# LPS_main.net
KiCad netlist of a schematic drawn in Altium Designer
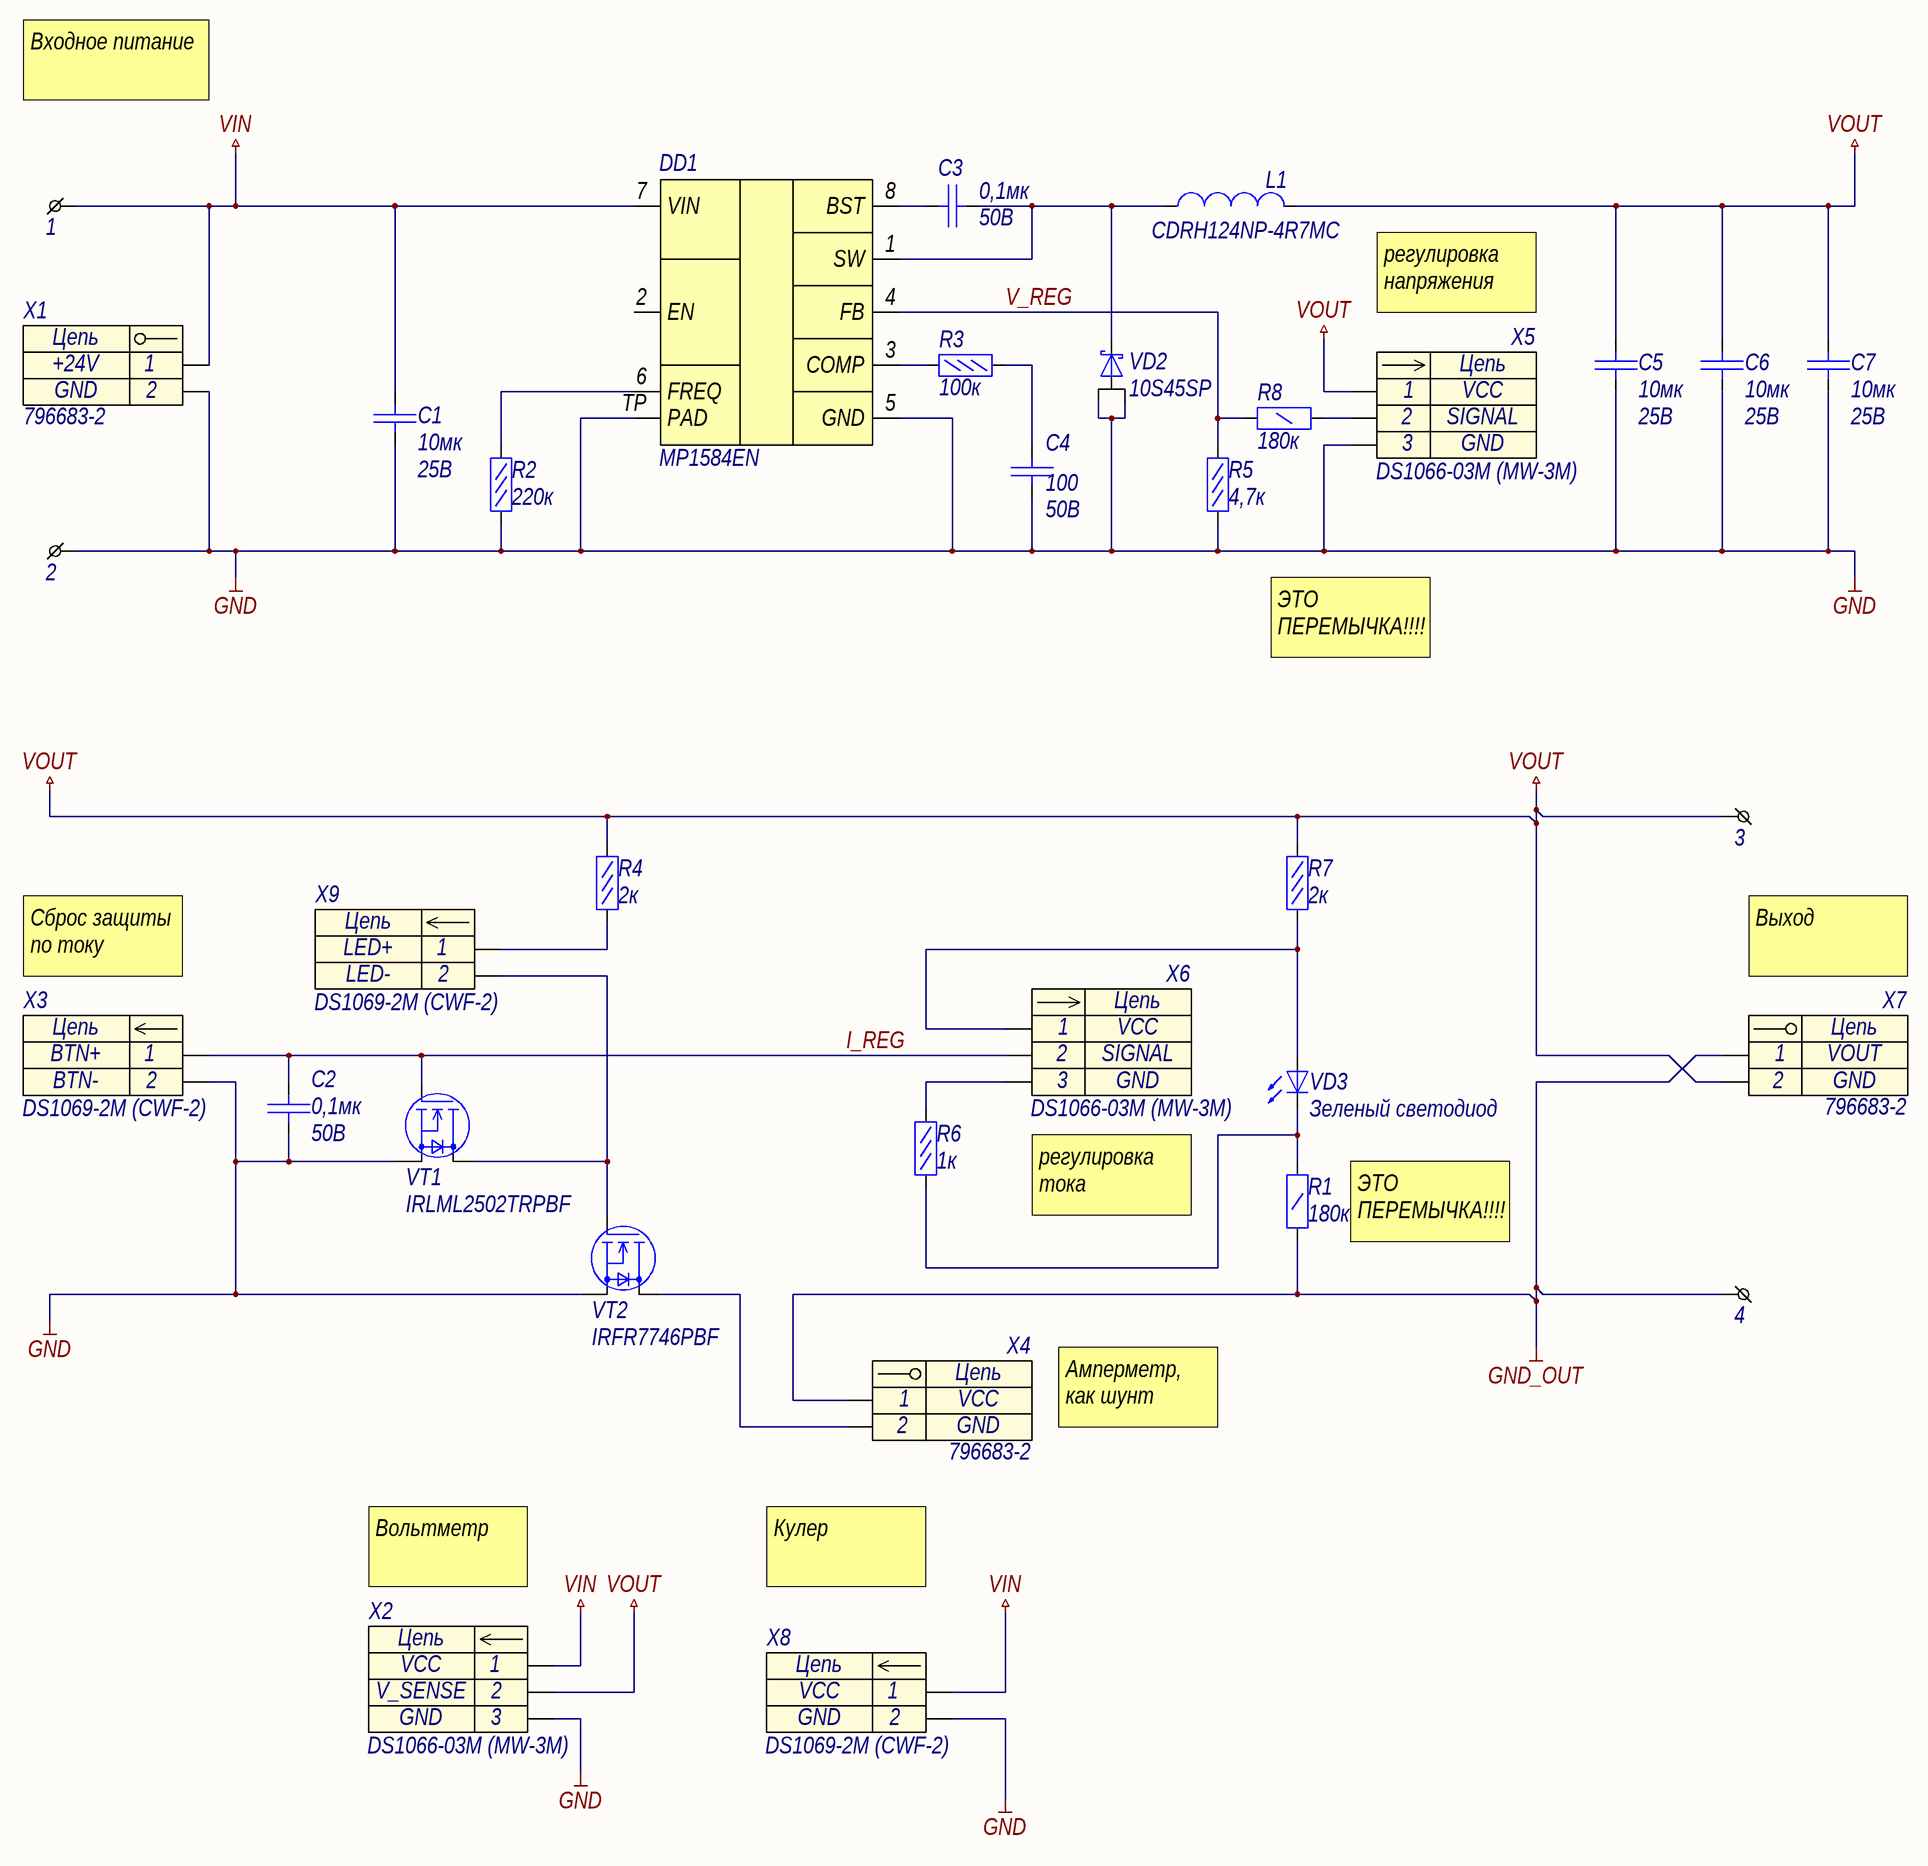
[diagram p0: LPS_main.SchDoc]

(export (version "E")
  (design (tool "Eeschema 10.0.6"))
  (components
    (comp (ref "1")
      (value "SOLDER_PAD")
      (footprint "PAD_5_8mm")
      (libsource (lib "mount_parts") (part "SOLDER_PAD"))
    )
    (comp (ref "2")
      (value "SOLDER_PAD")
      (footprint "PAD_5_8mm")
      (libsource (lib "mount_parts") (part "SOLDER_PAD"))
    )
    (comp (ref "3")
      (value "SOLDER_PAD")
      (footprint "PAD_5_8mm")
      (libsource (lib "mount_parts") (part "SOLDER_PAD"))
    )
    (comp (ref "4")
      (value "SOLDER_PAD")
      (footprint "PAD_5_8mm")
      (libsource (lib "mount_parts") (part "SOLDER_PAD"))
    )
    (comp (ref "C1")
      (value "10мк")
      (footprint "C1206")
      (description "Конденсатор кер. 10мкФ 25В")
      (fields (field (name "MANUFACTURER") "Yageo") (field (name "VOLTAGE") "25В"))
      (libsource (lib "capacitors") (part "CC1206KKX7R8BB106"))
    )
    (comp (ref "C2")
      (value "0,1мк")
      (footprint "C0603")
      (description "Конденсатор кер. 0,1мкФ 50В")
      (fields (field (name "MANUFACTURER") "Yageo") (field (name "VOLTAGE") "50В"))
      (libsource (lib "capacitors") (part "CC0603JPX7R9BB104"))
    )
    (comp (ref "C3")
      (value "0,1мк")
      (footprint "C0603")
      (description "Конденсатор кер. 0,1мкФ 50В")
      (fields (field (name "MANUFACTURER") "Yageo") (field (name "VOLTAGE") "50В"))
      (libsource (lib "capacitors") (part "CC0603JPX7R9BB104"))
    )
    (comp (ref "C4")
      (value "100")
      (footprint "C0603")
      (description "Конденсатор кер. 100пФ 50В")
      (fields (field (name "MANUFACTURER") "Yageo") (field (name "VOLTAGE") "50В"))
      (libsource (lib "capacitors") (part "CC0603JRNPO9BN101"))
    )
    (comp (ref "C5")
      (value "10мк")
      (footprint "C1206")
      (description "Конденсатор кер. 10мкФ 25В")
      (fields (field (name "MANUFACTURER") "Yageo") (field (name "VOLTAGE") "25В"))
      (libsource (lib "capacitors") (part "CC1206KKX7R8BB106"))
    )
    (comp (ref "C6")
      (value "10мк")
      (footprint "C1206")
      (description "Конденсатор кер. 10мкФ 25В")
      (fields (field (name "MANUFACTURER") "Yageo") (field (name "VOLTAGE") "25В"))
      (libsource (lib "capacitors") (part "CC1206KKX7R8BB106"))
    )
    (comp (ref "C7")
      (value "10мк")
      (footprint "C1206")
      (description "Конденсатор кер. 10мкФ 25В")
      (fields (field (name "MANUFACTURER") "Yageo") (field (name "VOLTAGE") "25В"))
      (libsource (lib "capacitors") (part "CC1206KKX7R8BB106"))
    )
    (comp (ref "DD1")
      (value "MP1584EN")
      (footprint "SOIC-8 with PAD")
      (description "регулируемый стабилизатор напряжения")
      (libsource (lib "ics") (part "MP1584EN"))
    )
    (comp (ref "L1")
      (value "CDRH124NP-4R7MC")
      (footprint "CDRH124")
      (description "Катушка с сердечником 4,7мкГн 0,8А")
      (libsource (lib "inductance") (part "CDRH124NP-4R7MC"))
    )
    (comp (ref "R1")
      (value "180к")
      (footprint "R1206")
      (description "Резистор 180к 0,25Вт 1%")
      (fields (field (name "MANUFACTURER") "YAGEO"))
      (libsource (lib "resistors") (part "RC1206FR-07180KL"))
    )
    (comp (ref "R2")
      (value "220к")
      (footprint "R0603")
      (description "Резистор 220кОм 0,1Вт 1%")
      (fields (field (name "MANUFACTURER") "YAGEO") (field (name "TOLERANCE") "1%"))
      (libsource (lib "resistors") (part "RC0603FR-07220KL"))
    )
    (comp (ref "R3")
      (value "100к")
      (footprint "R0603")
      (description "Резистор 100кОм 0,1Вт 1%")
      (fields (field (name "MANUFACTURER") "YAGEO") (field (name "TOLERANCE") "1%"))
      (libsource (lib "resistors") (part "RC0603FR-07100KL"))
    )
    (comp (ref "R4")
      (value "2к")
      (footprint "R0603")
      (description "Резистор 2кОм 0,063Вт 1%")
      (fields (field (name "MANUFACTURER") "YAGEO") (field (name "TOLERANCE") "1%"))
      (libsource (lib "resistors") (part "RC0603FR-072KL"))
    )
    (comp (ref "R5")
      (value "4,7к")
      (footprint "R0603")
      (description "Резистор 4,7кОм 0,063Вт 1%")
      (fields (field (name "MANUFACTURER") "YAGEO") (field (name "TOLERANCE") "1%"))
      (libsource (lib "resistors") (part "RC0603FR-074K7L"))
    )
    (comp (ref "R6")
      (value "1к")
      (footprint "R0603")
      (description "Резистор 1кОм 0,063Вт 1%")
      (fields (field (name "MANUFACTURER") "YAGEO") (field (name "TOLERANCE") "1%"))
      (libsource (lib "resistors") (part "RC0603FR-071KL"))
    )
    (comp (ref "R7")
      (value "2к")
      (footprint "R0603")
      (description "Резистор 2кОм 0,063Вт 1%")
      (fields (field (name "MANUFACTURER") "YAGEO") (field (name "TOLERANCE") "1%"))
      (libsource (lib "resistors") (part "RC0603FR-072KL"))
    )
    (comp (ref "R8")
      (value "180к")
      (footprint "R1206")
      (description "Резистор 180к 0,25Вт 1%")
      (fields (field (name "MANUFACTURER") "YAGEO"))
      (libsource (lib "") (part "RC1206FR-07180KL_1"))
    )
    (comp (ref "VD2")
      (value "10S45SP")
      (footprint "TO-277A")
      (description "Диод Шоттки 45В 10А")
      (fields (field (name "MANUFACTURER") "YFW") (field (name "NAME") "10S45SP"))
      (libsource (lib "diodes") (part "10S45SP"))
    )
    (comp (ref "VD3")
      (value "Зеленый светодиод")
      (footprint "VD0603")
      (description "Светодтод зеленый SMD Foryard Optoelectronics Co.")
      (libsource (lib "diodes") (part "FYLS-0603BUGC"))
    )
    (comp (ref "VT1")
      (value "IRLML2502TRPBF")
      (footprint "SOT23-3")
      (description "N-MOSFET 20В 4,5А")
      (fields (field (name "MANUFACTURER") "International Rectifier") (field (name "NAME") "IRLML2502TRPBF"))
      (libsource (lib "transistors") (part "IRLML2502TRPBF"))
    )
    (comp (ref "VT2")
      (value "IRFR7746PBF")
      (footprint "D-PAK")
      (description "N-MOSFET 75В, 56А")
      (fields (field (name "MANUFACTURER") "Internationa Rectifier") (field (name "NAME") "IRFR7746PBF"))
      (libsource (lib "transistors") (part "IRFR7746PBF"))
    )
    (comp (ref "X1")
      (value "796683-2")
      (footprint "796683-2")
      (description "Винтовой клеммник (наборный 2х2)")
      (fields (field (name "NAME") "796683-2"))
      (libsource (lib "") (part "796683-2_1"))
    )
    (comp (ref "X2")
      (value "DS1066-03M (MW-3M)")
      (footprint "MW-3M")
      (description "Разъем - 3 конт. прямая вилка на плату")
      (fields (field (name "NAME") "DS1066-03M (MW-3M)"))
      (libsource (lib "") (part "MW-3M_1"))
    )
    (comp (ref "X3")
      (value "DS1069-2M (CWF-2)")
      (footprint "CWF-2")
      (description "Разъем - 2 конт. прямая вилка на плату")
      (fields (field (name "NAME") "DS1069-2M (CWF-2)"))
      (libsource (lib "headers") (part "CWF-2"))
    )
    (comp (ref "X4")
      (value "796683-2")
      (footprint "796683-2")
      (description "Винтовой клеммник (наборный 2х2)")
      (fields (field (name "NAME") "796683-2"))
      (libsource (lib "headers") (part "796683-2"))
    )
    (comp (ref "X5")
      (value "DS1066-03M (MW-3M)")
      (footprint "MW-3M")
      (description "Разъем - 3 конт. прямая вилка на плату")
      (fields (field (name "NAME") "DS1066-03M (MW-3M)"))
      (libsource (lib "headers") (part "MW-3M"))
    )
    (comp (ref "X6")
      (value "DS1066-03M (MW-3M)")
      (footprint "MW-3M")
      (description "Разъем - 3 конт. прямая вилка на плату")
      (fields (field (name "NAME") "DS1066-03M (MW-3M)"))
      (libsource (lib "headers") (part "MW-3M"))
    )
    (comp (ref "X7")
      (value "796683-2")
      (footprint "796683-2")
      (description "Винтовой клеммник (наборный 2х2)")
      (fields (field (name "NAME") "796683-2"))
      (libsource (lib "headers") (part "796683-2"))
    )
    (comp (ref "X8")
      (value "DS1069-2M (CWF-2)")
      (footprint "CWF-2")
      (description "Разъем - 2 конт. прямая вилка на плату")
      (fields (field (name "NAME") "DS1069-2M (CWF-2)"))
      (libsource (lib "headers") (part "CWF-2"))
    )
    (comp (ref "X9")
      (value "DS1069-2M (CWF-2)")
      (footprint "CWF-2")
      (description "Разъем - 2 конт. прямая вилка на плату")
      (fields (field (name "NAME") "DS1069-2M (CWF-2)"))
      (libsource (lib "headers") (part "CWF-2"))
    )
  )
  (nets
    (net (code "1") (name "/I_REG") (class "Default")
      (node (ref "C2") (pin "2") (pinfunction "2_2") (pintype "passive"))
      (node (ref "VT1") (pin "1") (pinfunction "G_1") (pintype "passive"))
      (node (ref "X3") (pin "1") (pinfunction "1_1") (pintype "passive"))
      (node (ref "X6") (pin "2") (pinfunction "2_2") (pintype "passive"))
    )
    (net (code "2") (name "/V_REG") (class "Default")
      (node (ref "DD1") (pin "4") (pinfunction "FB_4") (pintype "passive"))
      (node (ref "R5") (pin "2") (pinfunction "2_2") (pintype "passive"))
      (node (ref "R8") (pin "2") (pinfunction "2_2") (pintype "passive"))
    )
    (net (code "3") (name "GND") (class "Default")
      (node (ref "2") (pin "1") (pinfunction "1_1") (pintype "passive"))
      (node (ref "C1") (pin "1") (pinfunction "1_1") (pintype "passive"))
      (node (ref "C2") (pin "1") (pinfunction "1_1") (pintype "passive"))
      (node (ref "C4") (pin "1") (pinfunction "1_1") (pintype "passive"))
      (node (ref "C5") (pin "1") (pinfunction "1_1") (pintype "passive"))
      (node (ref "C6") (pin "1") (pinfunction "1_1") (pintype "passive"))
      (node (ref "C7") (pin "1") (pinfunction "1_1") (pintype "passive"))
      (node (ref "DD1") (pin "5") (pinfunction "GND_5") (pintype "passive"))
      (node (ref "DD1") (pin "TP") (pinfunction "PAD_TP") (pintype "passive"))
      (node (ref "R2") (pin "1") (pinfunction "1_1") (pintype "passive"))
      (node (ref "R5") (pin "1") (pinfunction "1_1") (pintype "passive"))
      (node (ref "VD2") (pin "1") (pinfunction "A_1") (pintype "passive"))
      (node (ref "VD2") (pin "2") (pinfunction "A_2") (pintype "passive"))
      (node (ref "VT1") (pin "2") (pinfunction "S_2") (pintype "passive"))
      (node (ref "VT2") (pin "3") (pinfunction "S_3") (pintype "passive"))
      (node (ref "X1") (pin "2") (pinfunction "2_2") (pintype "passive"))
      (node (ref "X2") (pin "3") (pinfunction "3_3") (pintype "passive"))
      (node (ref "X3") (pin "2") (pinfunction "2_2") (pintype "passive"))
      (node (ref "X5") (pin "3") (pinfunction "3_3") (pintype "passive"))
      (node (ref "X8") (pin "2") (pinfunction "2_2") (pintype "passive"))
    )
    (net (code "4") (name "GND_OUT") (class "Default")
      (node (ref "4") (pin "1") (pinfunction "1_1") (pintype "passive"))
      (node (ref "R1") (pin "1") (pinfunction "1_1") (pintype "passive"))
      (node (ref "X4") (pin "1") (pinfunction "1_1") (pintype "passive"))
      (node (ref "X7") (pin "1") (pinfunction "1_1") (pintype "passive"))
    )
    (net (code "5") (name "Net-(C4-Pad2)") (class "Default")
      (node (ref "C4") (pin "2") (pinfunction "2_2") (pintype "passive"))
      (node (ref "R3") (pin "1") (pinfunction "1_1") (pintype "passive"))
    )
    (net (code "6") (name "Net-(DD1-BST)") (class "Default")
      (node (ref "C3") (pin "1") (pinfunction "1_1") (pintype "passive"))
      (node (ref "DD1") (pin "8") (pinfunction "BST_8") (pintype "passive"))
    )
    (net (code "7") (name "Net-(DD1-COMP)") (class "Default")
      (node (ref "DD1") (pin "3") (pinfunction "COMP_3") (pintype "passive"))
      (node (ref "R3") (pin "2") (pinfunction "2_2") (pintype "passive"))
    )
    (net (code "8") (name "Net-(DD1-FREQ)") (class "Default")
      (node (ref "DD1") (pin "6") (pinfunction "FREQ_6") (pintype "passive"))
      (node (ref "R2") (pin "2") (pinfunction "2_2") (pintype "passive"))
    )
    (net (code "9") (name "Net-(DD1-SW)") (class "Default")
      (node (ref "C3") (pin "2") (pinfunction "2_2") (pintype "passive"))
      (node (ref "DD1") (pin "1") (pinfunction "SW_1") (pintype "passive"))
      (node (ref "L1") (pin "1") (pinfunction "3_1") (pintype "passive"))
      (node (ref "VD2") (pin "3") (pinfunction "K_3") (pintype "passive"))
    )
    (net (code "10") (name "Net-(R4-Pad1)") (class "Default")
      (node (ref "R4") (pin "1") (pinfunction "1_1") (pintype "passive"))
      (node (ref "X9") (pin "1") (pinfunction "1_1") (pintype "passive"))
    )
    (net (code "11") (name "Net-(R6-Pad2)") (class "Default")
      (node (ref "R6") (pin "2") (pinfunction "2_2") (pintype "passive"))
      (node (ref "X6") (pin "3") (pinfunction "3_3") (pintype "passive"))
    )
    (net (code "12") (name "Net-(R8-Pad1)") (class "Default")
      (node (ref "R8") (pin "1") (pinfunction "1_1") (pintype "passive"))
      (node (ref "X5") (pin "2") (pinfunction "2_2") (pintype "passive"))
    )
    (net (code "13") (name "Net-(VD3-A)") (class "Default")
      (node (ref "R7") (pin "1") (pinfunction "1_1") (pintype "passive"))
      (node (ref "VD3") (pin "1") (pinfunction "A_1") (pintype "passive"))
      (node (ref "X6") (pin "1") (pinfunction "1_1") (pintype "passive"))
    )
    (net (code "14") (name "Net-(VD3-K)") (class "Default")
      (node (ref "R1") (pin "2") (pinfunction "2_2") (pintype "passive"))
      (node (ref "R6") (pin "1") (pinfunction "1_1") (pintype "passive"))
      (node (ref "VD3") (pin "2") (pinfunction "K_2") (pintype "passive"))
    )
    (net (code "15") (name "Net-(VT1-D)") (class "Default")
      (node (ref "VT1") (pin "3") (pinfunction "D_3") (pintype "passive"))
      (node (ref "VT2") (pin "1") (pinfunction "G_1") (pintype "passive"))
      (node (ref "X9") (pin "2") (pinfunction "2_2") (pintype "passive"))
    )
    (net (code "16") (name "Net-(VT2-D)") (class "Default")
      (node (ref "VT2") (pin "2") (pinfunction "D_2") (pintype "passive"))
      (node (ref "X4") (pin "2") (pinfunction "2_2") (pintype "passive"))
    )
    (net (code "17") (name "VIN") (class "Default")
      (node (ref "1") (pin "1") (pinfunction "1_1") (pintype "passive"))
      (node (ref "C1") (pin "2") (pinfunction "2_2") (pintype "passive"))
      (node (ref "DD1") (pin "7") (pinfunction "VIN_7") (pintype "passive"))
      (node (ref "X1") (pin "1") (pinfunction "1_1") (pintype "passive"))
      (node (ref "X2") (pin "1") (pinfunction "1_1") (pintype "passive"))
      (node (ref "X8") (pin "1") (pinfunction "1_1") (pintype "passive"))
    )
    (net (code "18") (name "VOUT") (class "Default")
      (node (ref "3") (pin "1") (pinfunction "1_1") (pintype "passive"))
      (node (ref "C5") (pin "2") (pinfunction "2_2") (pintype "passive"))
      (node (ref "C6") (pin "2") (pinfunction "2_2") (pintype "passive"))
      (node (ref "C7") (pin "2") (pinfunction "2_2") (pintype "passive"))
      (node (ref "L1") (pin "2") (pinfunction "4_2") (pintype "passive"))
      (node (ref "R4") (pin "2") (pinfunction "2_2") (pintype "passive"))
      (node (ref "R7") (pin "2") (pinfunction "2_2") (pintype "passive"))
      (node (ref "X2") (pin "2") (pinfunction "2_2") (pintype "passive"))
      (node (ref "X5") (pin "1") (pinfunction "1_1") (pintype "passive"))
      (node (ref "X7") (pin "2") (pinfunction "2_2") (pintype "passive"))
    )
    (net (code "19") (name "unconnected-(DD1-EN-Pad2)") (class "Default")
      (node (ref "DD1") (pin "2") (pinfunction "EN_2") (pintype "passive"))
    )
  )
)
